# STM32_Schematic.net
KiCad netlist of a schematic drawn in Altium Designer
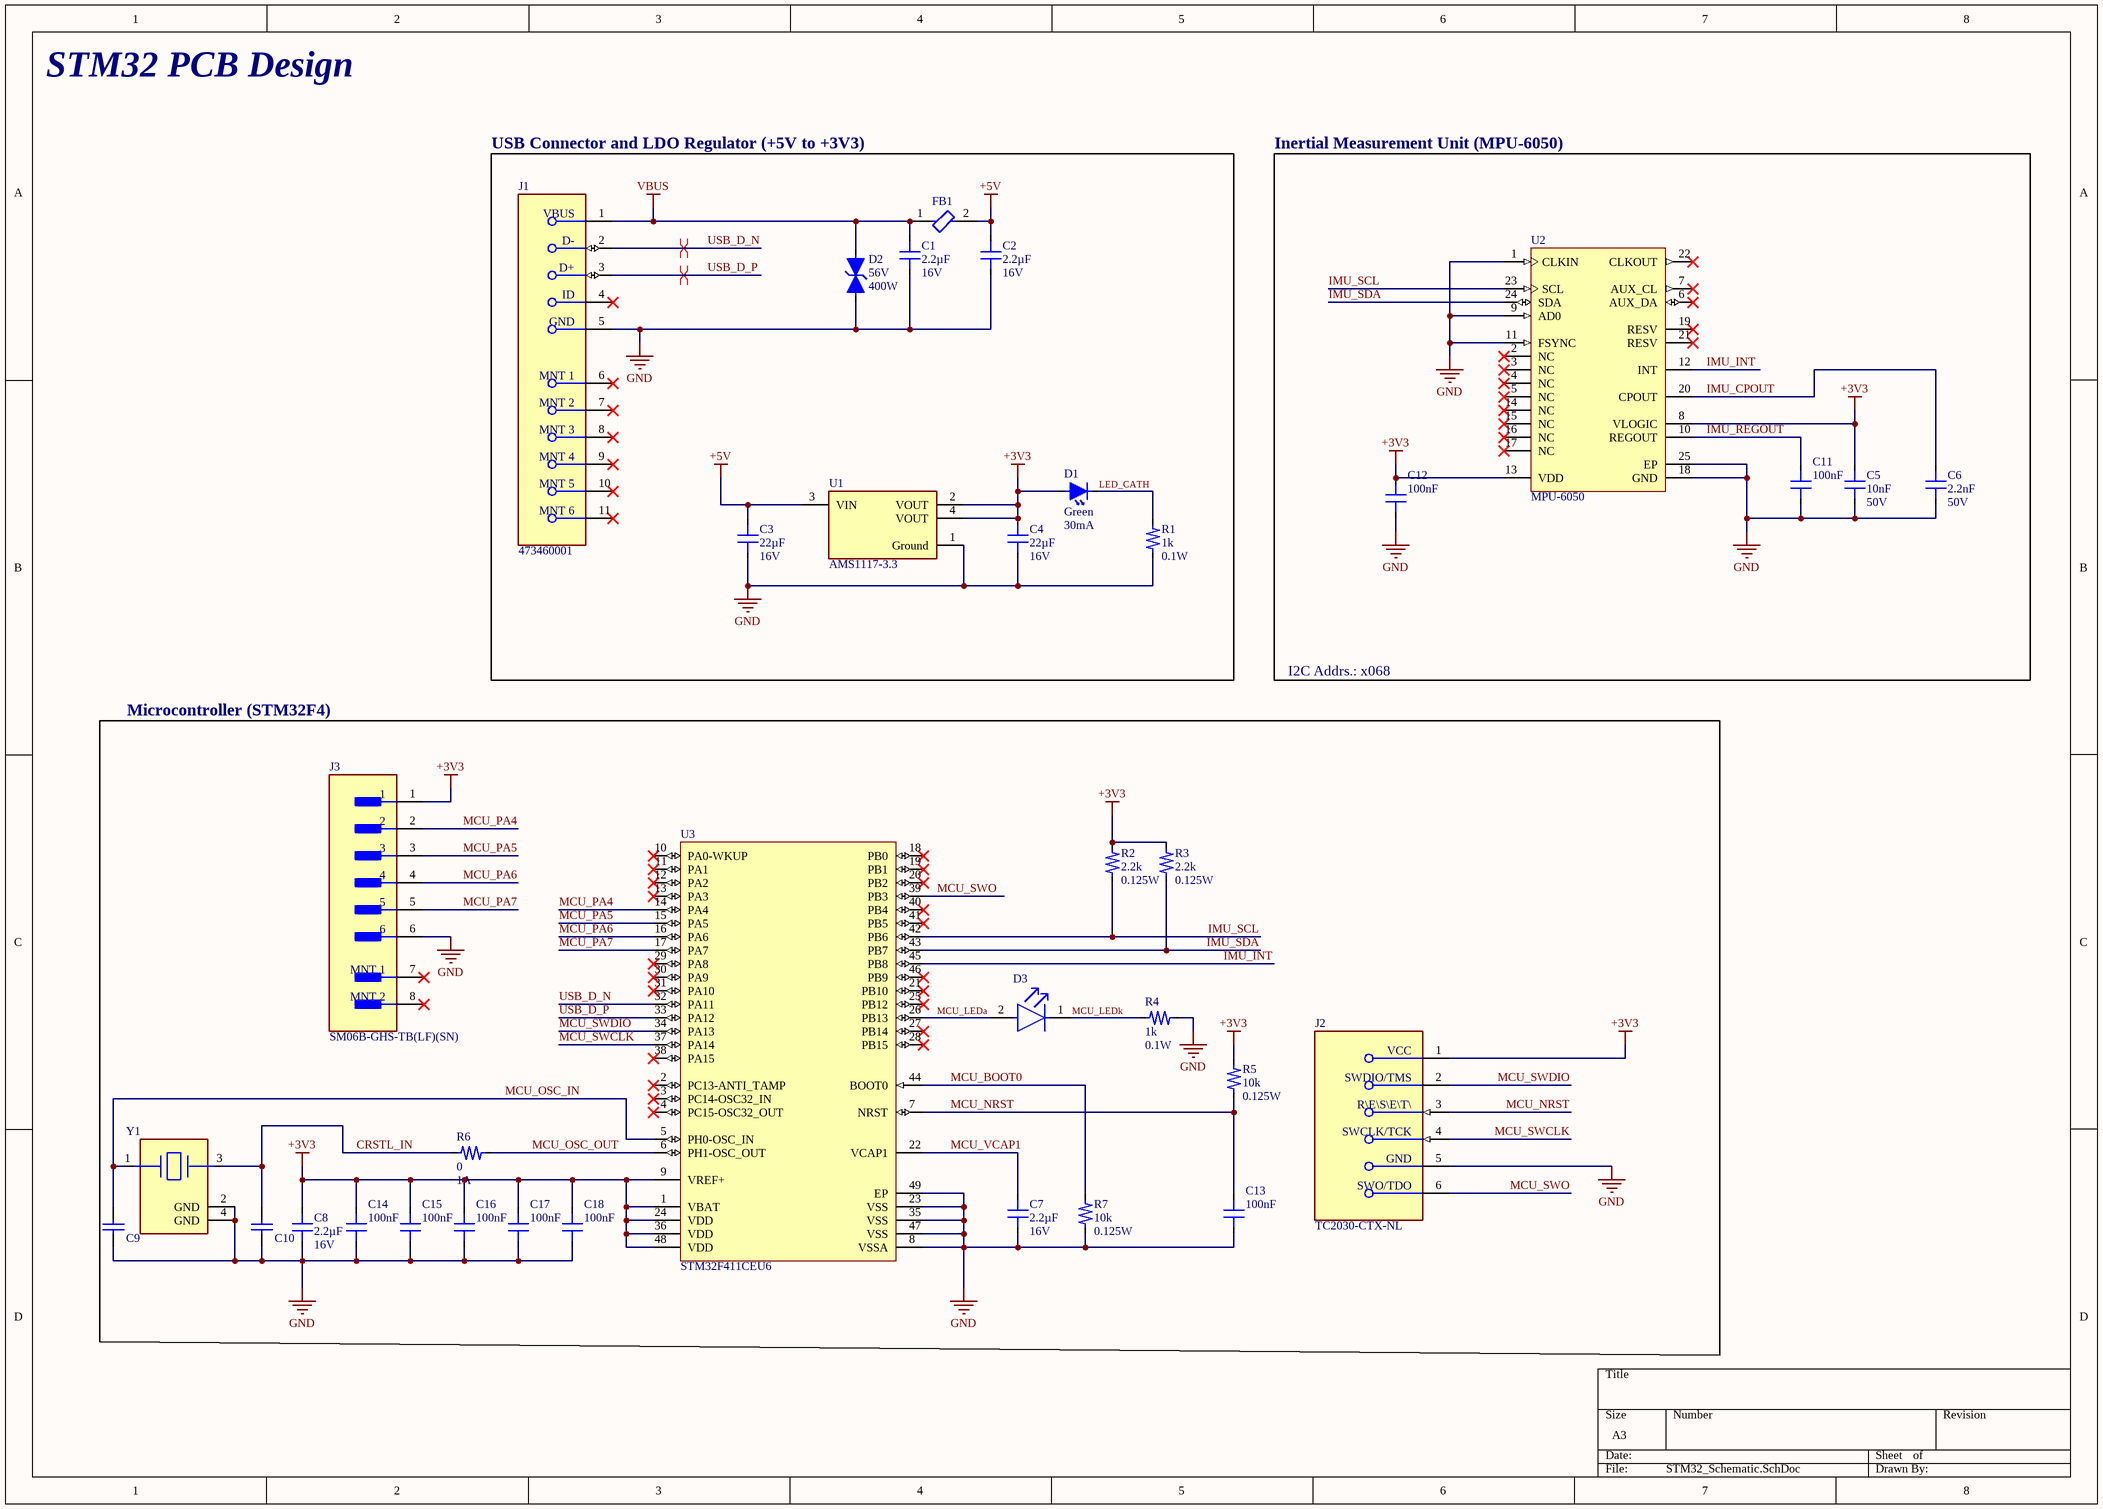
[diagram p0: STM32_Schematic.SchDoc]

(export (version "E")
  (design (tool "Eeschema 10.0.6"))
  (components
    (comp (ref "C1")
      (value "2.2µF")
      (footprint "C_0805")
      (fields
        (field (name "RATING") "16V")
        (field (name "PART NUMBER") "CC0805ZRY5V7BB225")
        (field (name "TOLERANCE") "20%")
      )
      (libsource (lib "BME Formula Racing Team") (part "CC0805ZRY5V7BB225"))
    )
    (comp (ref "C2")
      (value "2.2µF")
      (footprint "C_0805")
      (fields
        (field (name "RATING") "16V")
        (field (name "PART NUMBER") "CC0805ZRY5V7BB225")
        (field (name "TOLERANCE") "20%")
      )
      (libsource (lib "BME Formula Racing Team") (part "CC0805ZRY5V7BB225"))
    )
    (comp (ref "C3")
      (value "22µF")
      (footprint "C_1210")
      (fields
        (field (name "RATING") "16V")
        (field (name "TOLERANCE") "10%")
        (field (name "PART NUMBER") "CL32A226KOJNNNE")
      )
      (libsource (lib "BME Formula Racing Team") (part "CL32A226KOJNNNE"))
    )
    (comp (ref "C4")
      (value "22µF")
      (footprint "C_1210")
      (fields
        (field (name "RATING") "16V")
        (field (name "TOLERANCE") "10%")
        (field (name "PART NUMBER") "CL32A226KOJNNNE")
      )
      (libsource (lib "BME Formula Racing Team") (part "CL32A226KOJNNNE"))
    )
    (comp (ref "C5")
      (value "10nF")
      (footprint "C_0603")
      (fields
        (field (name "RATING") "50V")
        (field (name "PART NUMBER") "CC0603KRX7R9BB103")
        (field (name "TOLERANCE") "10%")
      )
      (libsource (lib "BME Formula Racing Team") (part "CC0603KRX7R9BB103"))
    )
    (comp (ref "C6")
      (value "2.2nF")
      (footprint "C_0805")
      (fields
        (field (name "RATING") "50V")
        (field (name "TOLERANCE") "5%")
        (field (name "PART NUMBER") "CC0805JKNP09BN222")
      )
      (libsource (lib "BME Formula Racing Team") (part "CC0805JKNP09BN222"))
    )
    (comp (ref "C7")
      (value "2.2µF")
      (footprint "C_0805")
      (fields
        (field (name "RATING") "16V")
        (field (name "PART NUMBER") "CC0805ZRY5V7BB225")
        (field (name "TOLERANCE") "20%")
      )
      (libsource (lib "BME Formula Racing Team") (part "CC0805ZRY5V7BB225"))
    )
    (comp (ref "C8")
      (value "2.2µF")
      (footprint "C_0805")
      (fields
        (field (name "RATING") "16V")
        (field (name "PART NUMBER") "CC0805ZRY5V7BB225")
        (field (name "TOLERANCE") "20%")
      )
      (libsource (lib "BME Formula Racing Team") (part "CC0805ZRY5V7BB225"))
    )
    (comp (ref "C9")
      (value "885392005106")
      (footprint "WCAP-CSRF_0402")
      (description "WCAP-CSRF Multilayer Ceramic Chip Capacitor High Frequency, size 0402, NP0 Class I, 10pF, 50VDC")
      (fields (field (name "MANUFACTURER") "Wurth Elektronik"))
      (libsource (lib "BME Formula Racing Team") (part "885392005147"))
    )
    (comp (ref "C10")
      (value "885392005106")
      (footprint "WCAP-CSRF_0402")
      (description "WCAP-CSRF Multilayer Ceramic Chip Capacitor High Frequency, size 0402, NP0 Class I, 10pF, 50VDC")
      (fields (field (name "MANUFACTURER") "Wurth Elektronik"))
      (libsource (lib "BME Formula Racing Team") (part "885392005147"))
    )
    (comp (ref "C11")
      (value "100nF")
      (footprint "CAPC1005X55N")
      (description "Multilayer Ceramic Capacitor, 0.1 uF, 16 V, ï¿½ 10%, X7R, 0402 [1005 Metric]")
      (fields (field (name "TOLERANCE") "10%") (field (name "MOUSER PART NUMBER") "187-CL05B104KO5NNNC"))
      (libsource (lib "BME Formula Racing Team") (part "CL10A105KA8NNNC"))
    )
    (comp (ref "C12")
      (value "100nF")
      (footprint "CAPC1005X55N")
      (description "Multilayer Ceramic Capacitor, 0.1 uF, 16 V, ï¿½ 10%, X7R, 0402 [1005 Metric]")
      (fields (field (name "TOLERANCE") "10%") (field (name "MOUSER PART NUMBER") "187-CL05B104KO5NNNC"))
      (libsource (lib "BME Formula Racing Team") (part "CL10A105KA8NNNC"))
    )
    (comp (ref "C13")
      (value "100nF")
      (footprint "CAPC1005X55N")
      (description "Multilayer Ceramic Capacitor, 0.1 uF, 16 V, ï¿½ 10%, X7R, 0402 [1005 Metric]")
      (fields (field (name "TOLERANCE") "10%") (field (name "MOUSER PART NUMBER") "187-CL05B104KO5NNNC"))
      (libsource (lib "BME Formula Racing Team") (part "CL10A105KA8NNNC"))
    )
    (comp (ref "C14")
      (value "100nF")
      (footprint "CAPC1005X55N")
      (description "Multilayer Ceramic Capacitor, 0.1 uF, 16 V, ï¿½ 10%, X7R, 0402 [1005 Metric]")
      (fields (field (name "TOLERANCE") "10%") (field (name "MOUSER PART NUMBER") "187-CL05B104KO5NNNC"))
      (libsource (lib "BME Formula Racing Team") (part "CL10A105KA8NNNC"))
    )
    (comp (ref "C15")
      (value "100nF")
      (footprint "CAPC1005X55N")
      (description "Multilayer Ceramic Capacitor, 0.1 uF, 16 V, ï¿½ 10%, X7R, 0402 [1005 Metric]")
      (fields (field (name "TOLERANCE") "10%") (field (name "MOUSER PART NUMBER") "187-CL05B104KO5NNNC"))
      (libsource (lib "BME Formula Racing Team") (part "CL10A105KA8NNNC"))
    )
    (comp (ref "C16")
      (value "100nF")
      (footprint "CAPC1005X55N")
      (description "Multilayer Ceramic Capacitor, 0.1 uF, 16 V, ï¿½ 10%, X7R, 0402 [1005 Metric]")
      (fields (field (name "TOLERANCE") "10%") (field (name "MOUSER PART NUMBER") "187-CL05B104KO5NNNC"))
      (libsource (lib "BME Formula Racing Team") (part "CL10A105KA8NNNC"))
    )
    (comp (ref "C17")
      (value "100nF")
      (footprint "CAPC1005X55N")
      (description "Multilayer Ceramic Capacitor, 0.1 uF, 16 V, ï¿½ 10%, X7R, 0402 [1005 Metric]")
      (fields (field (name "TOLERANCE") "10%") (field (name "MOUSER PART NUMBER") "187-CL05B104KO5NNNC"))
      (libsource (lib "BME Formula Racing Team") (part "CL10A105KA8NNNC"))
    )
    (comp (ref "C18")
      (value "100nF")
      (footprint "CAPC1005X55N")
      (description "Multilayer Ceramic Capacitor, 0.1 uF, 16 V, ï¿½ 10%, X7R, 0402 [1005 Metric]")
      (fields (field (name "TOLERANCE") "10%") (field (name "MOUSER PART NUMBER") "187-CL05B104KO5NNNC"))
      (libsource (lib "BME Formula Racing Team") (part "CL10A105KA8NNNC"))
    )
    (comp (ref "D1")
      (value "Green")
      (footprint "LED_0603")
      (fields (field (name "RATING") "30mA") (field (name "PART NUMBER") "FYLS-0603UGC"))
      (libsource (lib "BME Formula Racing Team") (part "FYLS-0603UGC"))
    )
    (comp (ref "D2")
      (value "56V")
      (footprint "SMA")
      (description "bidirectional")
      (fields (field (name "RATING") "400W") (field (name "PART NUMBER") "SMAJ48CA"))
      (libsource (lib "BME Formula Racing Team") (part "SMAJ5.0A"))
    )
    (comp (ref "D3")
      (value "LXZ1-PD02")
      (footprint "FP-LXZ1-PD02-MFG")
      (description "LUXEON Z High Power SMT LED Emitter Red Lambertian 500mA 2.15 V")
      (libsource (lib "Altium Content Vault") (part "8706943c75ba83719d021d2fdc84c58"))
    )
    (comp (ref "FB1")
      (value "MMZ1608R121ATA00")
      (footprint "FP-MMZ1608-0_8-IPC_C")
      (description "Signal Line Ferrite Bead 120Ω  @ 100MHz 500mA DCR 180mΩ SMD 0603")
      (fields (field (name "TOLERANCE") "25%"))
      (libsource (lib "Altium Content Vault") (part "5f30dd21d616792df468990f7003faa"))
    )
    (comp (ref "J1")
      (value "473460001")
      (footprint "FP-473460001-MFG")
      (description "CONN RCPT USB2.0 MICRO B SMD R/A")
      (fields
        (field (name "OCTOPART") "https://octopart.com/47346-0001-molex-7164928")
        (field (name "MANUFACTURER") "Molex")
      )
      (libsource (lib "Altium Content Vault") (part "53ae1f1d9b557310b43ca686e5bb76a"))
    )
    (comp (ref "J2")
      (value "TC2030-CTX-NL")
      (footprint "FP-TC2030-CTX-NL-MFG")
      (description "6-Pin “No legs” TC2030 Plug-of-Nails™ Cable for use with ARM Cortex processors")
      (libsource (lib "Altium Content Vault") (part "e3fe093a55dc37473f431e03719485e"))
    )
    (comp (ref "J3")
      (value "SM06B-GHS-TB(LF)(SN)")
      (footprint "FP-SM06B-GHS-TB_LF_SN-MFG")
      (description "CONN HEADER SMD R/A 6POS 1.25MM")
      (libsource (lib "Altium Content Vault") (part "ed24c53d9ba001d1a2a686240a95171"))
    )
    (comp (ref "R1")
      (value "1k")
      (footprint "R_0603")
      (fields
        (field (name "RATING") "0.1W")
        (field (name "NI PART NUMBER") "713776-01")
        (field (name "PART NUMBER") "CR-03FL7----1K")
        (field (name "TOLERANCE") "1%")
      )
      (libsource (lib "BME Formula Racing Team") (part "CR-03FL7----1K"))
    )
    (comp (ref "R2")
      (value "2.2k")
      (footprint "R_0805")
      (fields
        (field (name "RATING") "0.125W")
        (field (name "TOLERANCE") "1%")
        (field (name "PART NUMBER") "CR-05FL7---2K2")
      )
      (libsource (lib "BME Formula Racing Team") (part "CR-05FL7---2K2"))
    )
    (comp (ref "R3")
      (value "2.2k")
      (footprint "R_0805")
      (fields
        (field (name "RATING") "0.125W")
        (field (name "TOLERANCE") "1%")
        (field (name "PART NUMBER") "CR-05FL7---2K2")
      )
      (libsource (lib "BME Formula Racing Team") (part "CR-05FL7---2K2"))
    )
    (comp (ref "R4")
      (value "1k")
      (footprint "R_0603")
      (fields
        (field (name "RATING") "0.1W")
        (field (name "NI PART NUMBER") "713776-01")
        (field (name "PART NUMBER") "CR-03FL7----1K")
        (field (name "TOLERANCE") "1%")
      )
      (libsource (lib "") (part "CR-03FL7----1K_1"))
    )
    (comp (ref "R5")
      (value "10k")
      (footprint "R_0805")
      (fields
        (field (name "RATING") "0.125W")
        (field (name "PART NUMBER") "CR-05FL7---10K")
        (field (name "TOLERANCE") "1%")
      )
      (libsource (lib "BME Formula Racing Team") (part "CR-05FL7---10K"))
    )
    (comp (ref "R6")
      (value "0")
      (footprint "R_0603")
      (fields
        (field (name "RATING") "1A")
        (field (name "PART NUMBER") "CR-03JL7----0R")
        (field (name "NI PART NUMBER") "611560-01")
        (field (name "TOLERANCE") "5%")
      )
      (libsource (lib "BME Formula Racing Team") (part "CR-03JL7----0R"))
    )
    (comp (ref "R7")
      (value "10k")
      (footprint "R_0805")
      (fields
        (field (name "RATING") "0.125W")
        (field (name "PART NUMBER") "CR-05FL7---10K")
        (field (name "TOLERANCE") "1%")
      )
      (libsource (lib "BME Formula Racing Team") (part "CR-05FL7---10K"))
    )
    (comp (ref "U1")
      (value "AMS1117-3.3")
      (footprint "FP-AMS1117-IPC_C")
      (description "LDO Voltage Regulators 1A, 3.3V")
      (fields
        (field (name "OCTOPART") "https://octopart.com/ams1117-3.3-advanced+monolithic+systems-25899300")
        (field (name "MANUFACTURER") "Advanced Monolithic Systems")
      )
      (libsource (lib "Altium Content Vault") (part "8bdbb5f8e77002000e30dd2845d0354"))
    )
    (comp (ref "U2")
      (value "MPU-6050")
      (footprint "IS-QFN-24_V")
      (fields (field (name "MANUFACTURER") "InvenSense"))
      (libsource (lib "Altium Content Vault") (part "IS-MPU-6050-QFN-24"))
    )
    (comp (ref "U3")
      (value "STM32F411CEU6")
      (footprint "STM-UFQFPN48_L")
      (libsource (lib "Altium Content Vault") (part "MC-ARM-STM32F411-UFQFPN48"))
    )
    (comp (ref "Y1")
      (value "ABM11-20.000MHZ-B7G-T")
      (footprint "FP-ABM11-MFG")
      (description "Crystal 20MHz ±15ppm 10pF SMD-4 2mm x 1.6mm")
      (fields (field (name "TOLERANCE") "15ppm"))
      (libsource (lib "Altium Content Vault") (part "b3c1237d77310e73098bcf11eecb25f"))
    )
  )
  (nets
    (net (code "1") (name "+3V3") (class "Default")
      (node (ref "C12") (pin "1") (pinfunction "C1_1") (pintype "passive"))
      (node (ref "C14") (pin "1") (pinfunction "C1_1") (pintype "passive"))
      (node (ref "C15") (pin "1") (pinfunction "C1_1") (pintype "passive"))
      (node (ref "C16") (pin "1") (pinfunction "C1_1") (pintype "passive"))
      (node (ref "C17") (pin "1") (pinfunction "C1_1") (pintype "passive"))
      (node (ref "C18") (pin "1") (pinfunction "C1_1") (pintype "passive"))
      (node (ref "C4") (pin "2") (pinfunction "C2_2") (pintype "passive"))
      (node (ref "C5") (pin "2") (pinfunction "C2_2") (pintype "passive"))
      (node (ref "C8") (pin "2") (pinfunction "C2_2") (pintype "passive"))
      (node (ref "D1") (pin "2") (pinfunction "DA_2") (pintype "passive"))
      (node (ref "J2") (pin "1") (pinfunction "VCC_1") (pintype "power_in"))
      (node (ref "J3") (pin "1") (pinfunction "1_1") (pintype "passive"))
      (node (ref "R2") (pin "2") (pinfunction "R2_2") (pintype "passive"))
      (node (ref "R3") (pin "2") (pinfunction "R2_2") (pintype "passive"))
      (node (ref "R5") (pin "2") (pinfunction "R2_2") (pintype "passive"))
      (node (ref "U1") (pin "2") (pinfunction "VOUT_2") (pintype "passive"))
      (node (ref "U1") (pin "4") (pinfunction "VOUT_4") (pintype "passive"))
      (node (ref "U2") (pin "13") (pinfunction "VDD_13") (pintype "power_in"))
      (node (ref "U2") (pin "8") (pinfunction "VLOGIC_8") (pintype "power_in"))
      (node (ref "U3") (pin "1") (pinfunction "VBAT_1") (pintype "power_in"))
      (node (ref "U3") (pin "24") (pinfunction "VDD_24") (pintype "power_in"))
      (node (ref "U3") (pin "36") (pinfunction "VDD_36") (pintype "power_in"))
      (node (ref "U3") (pin "48") (pinfunction "VDD_48") (pintype "power_in"))
      (node (ref "U3") (pin "9") (pinfunction "VREF+_9") (pintype "power_in"))
    )
    (net (code "2") (name "+5V") (class "Default")
      (node (ref "C2") (pin "2") (pinfunction "C2_2") (pintype "passive"))
      (node (ref "C3") (pin "2") (pinfunction "C2_2") (pintype "passive"))
      (node (ref "FB1") (pin "2") (pinfunction "2_2") (pintype "passive"))
      (node (ref "U1") (pin "3") (pinfunction "VIN_3") (pintype "power_in"))
    )
    (net (code "3") (name "/CRSTL_IN") (class "Default")
      (node (ref "C10") (pin "2") (pinfunction "2_2") (pintype "passive"))
      (node (ref "R6") (pin "1") (pinfunction "R1_1") (pintype "passive"))
      (node (ref "Y1") (pin "3") (pinfunction "3_3") (pintype "passive"))
    )
    (net (code "4") (name "/IMU_CPOUT") (class "Default")
      (node (ref "C6") (pin "2") (pinfunction "C2_2") (pintype "passive"))
      (node (ref "U2") (pin "20") (pinfunction "CPOUT_20") (pintype "passive"))
    )
    (net (code "5") (name "/IMU_INT") (class "Default")
      (node (ref "U2") (pin "12") (pinfunction "INT_12") (pintype "open_collector"))
      (node (ref "U3") (pin "45") (pinfunction "PB8_45") (pintype "bidirectional"))
    )
    (net (code "6") (name "/IMU_REGOUT") (class "Default")
      (node (ref "C11") (pin "1") (pinfunction "C1_1") (pintype "passive"))
      (node (ref "U2") (pin "10") (pinfunction "REGOUT_10") (pintype "passive"))
    )
    (net (code "7") (name "/IMU_SCL") (class "Default")
      (node (ref "R2") (pin "1") (pinfunction "R1_1") (pintype "passive"))
      (node (ref "U2") (pin "23") (pinfunction "SCL_23") (pintype "input"))
      (node (ref "U3") (pin "42") (pinfunction "PB6_42") (pintype "bidirectional"))
    )
    (net (code "8") (name "/IMU_SDA") (class "Default")
      (node (ref "R3") (pin "1") (pinfunction "R1_1") (pintype "passive"))
      (node (ref "U2") (pin "24") (pinfunction "SDA_24") (pintype "bidirectional"))
      (node (ref "U3") (pin "43") (pinfunction "PB7_43") (pintype "bidirectional"))
    )
    (net (code "9") (name "/LED_CATH") (class "Default")
      (node (ref "D1") (pin "1") (pinfunction "DC_1") (pintype "passive"))
      (node (ref "R1") (pin "2") (pinfunction "R2_2") (pintype "passive"))
    )
    (net (code "10") (name "/MCU_BOOT0") (class "Default")
      (node (ref "R7") (pin "2") (pinfunction "R2_2") (pintype "passive"))
      (node (ref "U3") (pin "44") (pinfunction "BOOT0_44") (pintype "input"))
    )
    (net (code "11") (name "/MCU_LEDa") (class "Default")
      (node (ref "D3") (pin "2") (pinfunction "A_2") (pintype "passive"))
      (node (ref "U3") (pin "26") (pinfunction "PB13_26") (pintype "bidirectional"))
    )
    (net (code "12") (name "/MCU_LEDk") (class "Default")
      (node (ref "D3") (pin "1") (pinfunction "C_1") (pintype "passive"))
      (node (ref "R4") (pin "2") (pinfunction "R2_2") (pintype "passive"))
    )
    (net (code "13") (name "/MCU_NRST") (class "Default")
      (node (ref "C13") (pin "1") (pinfunction "C1_1") (pintype "passive"))
      (node (ref "J2") (pin "3") (pinfunction "~{RESET}_3") (pintype "input"))
      (node (ref "R5") (pin "1") (pinfunction "R1_1") (pintype "passive"))
      (node (ref "U3") (pin "7") (pinfunction "NRST_7") (pintype "bidirectional"))
    )
    (net (code "14") (name "/MCU_OSC_IN") (class "Default")
      (node (ref "C9") (pin "2") (pinfunction "2_2") (pintype "passive"))
      (node (ref "U3") (pin "5") (pinfunction "PH0-OSC_IN_5") (pintype "bidirectional"))
      (node (ref "Y1") (pin "1") (pinfunction "1_1") (pintype "passive"))
    )
    (net (code "15") (name "/MCU_OSC_OUT") (class "Default")
      (node (ref "R6") (pin "2") (pinfunction "R2_2") (pintype "passive"))
      (node (ref "U3") (pin "6") (pinfunction "PH1-OSC_OUT_6") (pintype "bidirectional"))
    )
    (net (code "16") (name "/MCU_PA4") (class "Default")
      (node (ref "J3") (pin "2") (pinfunction "2_2") (pintype "passive"))
      (node (ref "U3") (pin "14") (pinfunction "PA4_14") (pintype "bidirectional"))
    )
    (net (code "17") (name "/MCU_PA5") (class "Default")
      (node (ref "J3") (pin "3") (pinfunction "3_3") (pintype "passive"))
      (node (ref "U3") (pin "15") (pinfunction "PA5_15") (pintype "bidirectional"))
    )
    (net (code "18") (name "/MCU_PA6") (class "Default")
      (node (ref "J3") (pin "4") (pinfunction "4_4") (pintype "passive"))
      (node (ref "U3") (pin "16") (pinfunction "PA6_16") (pintype "bidirectional"))
    )
    (net (code "19") (name "/MCU_PA7") (class "Default")
      (node (ref "J3") (pin "5") (pinfunction "5_5") (pintype "passive"))
      (node (ref "U3") (pin "17") (pinfunction "PA7_17") (pintype "bidirectional"))
    )
    (net (code "20") (name "/MCU_SWCLK") (class "Default")
      (node (ref "J2") (pin "4") (pinfunction "SWCLK/TCK_4") (pintype "input"))
      (node (ref "U3") (pin "37") (pinfunction "PA14_37") (pintype "bidirectional"))
    )
    (net (code "21") (name "/MCU_SWDIO") (class "Default")
      (node (ref "J2") (pin "2") (pinfunction "SWDIO/TMS_2") (pintype "passive"))
      (node (ref "U3") (pin "34") (pinfunction "PA13_34") (pintype "bidirectional"))
    )
    (net (code "22") (name "/MCU_SWO") (class "Default")
      (node (ref "J2") (pin "6") (pinfunction "SWO/TDO_6") (pintype "passive"))
      (node (ref "U3") (pin "39") (pinfunction "PB3_39") (pintype "bidirectional"))
    )
    (net (code "23") (name "/MCU_VCAP1") (class "Default")
      (node (ref "C7") (pin "2") (pinfunction "C2_2") (pintype "passive"))
      (node (ref "U3") (pin "22") (pinfunction "VCAP1_22") (pintype "passive"))
    )
    (net (code "24") (name "/USB_D_N") (class "Default")
      (node (ref "J1") (pin "2") (pinfunction "D-_2") (pintype "bidirectional"))
      (node (ref "U3") (pin "32") (pinfunction "PA11_32") (pintype "bidirectional"))
    )
    (net (code "25") (name "/USB_D_P") (class "Default")
      (node (ref "J1") (pin "3") (pinfunction "D+_3") (pintype "bidirectional"))
      (node (ref "U3") (pin "33") (pinfunction "PA12_33") (pintype "bidirectional"))
    )
    (net (code "26") (name "GND") (class "Default")
      (node (ref "C1") (pin "1") (pinfunction "C1_1") (pintype "passive"))
      (node (ref "C10") (pin "1") (pinfunction "1_1") (pintype "passive"))
      (node (ref "C11") (pin "2") (pinfunction "C2_2") (pintype "passive"))
      (node (ref "C12") (pin "2") (pinfunction "C2_2") (pintype "passive"))
      (node (ref "C13") (pin "2") (pinfunction "C2_2") (pintype "passive"))
      (node (ref "C14") (pin "2") (pinfunction "C2_2") (pintype "passive"))
      (node (ref "C15") (pin "2") (pinfunction "C2_2") (pintype "passive"))
      (node (ref "C16") (pin "2") (pinfunction "C2_2") (pintype "passive"))
      (node (ref "C17") (pin "2") (pinfunction "C2_2") (pintype "passive"))
      (node (ref "C18") (pin "2") (pinfunction "C2_2") (pintype "passive"))
      (node (ref "C2") (pin "1") (pinfunction "C1_1") (pintype "passive"))
      (node (ref "C3") (pin "1") (pinfunction "C1_1") (pintype "passive"))
      (node (ref "C4") (pin "1") (pinfunction "C1_1") (pintype "passive"))
      (node (ref "C5") (pin "1") (pinfunction "C1_1") (pintype "passive"))
      (node (ref "C6") (pin "1") (pinfunction "C1_1") (pintype "passive"))
      (node (ref "C7") (pin "1") (pinfunction "C1_1") (pintype "passive"))
      (node (ref "C8") (pin "1") (pinfunction "C1_1") (pintype "passive"))
      (node (ref "C9") (pin "1") (pinfunction "1_1") (pintype "passive"))
      (node (ref "D2") (pin "2") (pinfunction "DA_2") (pintype "passive"))
      (node (ref "J1") (pin "5") (pinfunction "GND_5") (pintype "power_in"))
      (node (ref "J2") (pin "5") (pinfunction "GND_5") (pintype "power_in"))
      (node (ref "J3") (pin "6") (pinfunction "6_6") (pintype "passive"))
      (node (ref "R1") (pin "1") (pinfunction "R1_1") (pintype "passive"))
      (node (ref "R4") (pin "1") (pinfunction "R1_1") (pintype "passive"))
      (node (ref "R7") (pin "1") (pinfunction "R1_1") (pintype "passive"))
      (node (ref "U1") (pin "1") (pinfunction "Ground_1") (pintype "power_in"))
      (node (ref "U2") (pin "1") (pinfunction "CLKIN_1") (pintype "input"))
      (node (ref "U2") (pin "11") (pinfunction "FSYNC_11") (pintype "input"))
      (node (ref "U2") (pin "18") (pinfunction "GND_18") (pintype "power_in"))
      (node (ref "U2") (pin "25") (pinfunction "EP_25") (pintype "power_in"))
      (node (ref "U2") (pin "9") (pinfunction "AD0_9") (pintype "input"))
      (node (ref "U3") (pin "23") (pinfunction "VSS_23") (pintype "power_in"))
      (node (ref "U3") (pin "35") (pinfunction "VSS_35") (pintype "power_in"))
      (node (ref "U3") (pin "47") (pinfunction "VSS_47") (pintype "power_in"))
      (node (ref "U3") (pin "49") (pinfunction "EP_49") (pintype "power_in"))
      (node (ref "U3") (pin "8") (pinfunction "VSSA_8") (pintype "power_in"))
      (node (ref "Y1") (pin "2") (pinfunction "GND_2") (pintype "power_in"))
      (node (ref "Y1") (pin "4") (pinfunction "GND_4") (pintype "power_in"))
    )
    (net (code "27") (name "VBUS") (class "Default")
      (node (ref "C1") (pin "2") (pinfunction "C2_2") (pintype "passive"))
      (node (ref "D2") (pin "1") (pinfunction "DC_1") (pintype "passive"))
      (node (ref "FB1") (pin "1") (pinfunction "1_1") (pintype "passive"))
      (node (ref "J1") (pin "1") (pinfunction "VBUS_1") (pintype "power_in"))
    )
    (net (code "28") (name "unconnected-(J1-ID-Pad4)") (class "Default")
      (node (ref "J1") (pin "4") (pinfunction "ID_4") (pintype "passive+no_connect"))
    )
    (net (code "29") (name "unconnected-(J1-MNT_1-Pad6)") (class "Default")
      (node (ref "J1") (pin "6") (pinfunction "MNT_1_6") (pintype "passive+no_connect"))
    )
    (net (code "30") (name "unconnected-(J1-MNT_2-Pad7)") (class "Default")
      (node (ref "J1") (pin "7") (pinfunction "MNT_2_7") (pintype "passive+no_connect"))
    )
    (net (code "31") (name "unconnected-(J1-MNT_3-Pad8)") (class "Default")
      (node (ref "J1") (pin "8") (pinfunction "MNT_3_8") (pintype "passive+no_connect"))
    )
    (net (code "32") (name "unconnected-(J1-MNT_4-Pad9)") (class "Default")
      (node (ref "J1") (pin "9") (pinfunction "MNT_4_9") (pintype "passive+no_connect"))
    )
    (net (code "33") (name "unconnected-(J1-MNT_5-Pad10)") (class "Default")
      (node (ref "J1") (pin "10") (pinfunction "MNT_5_10") (pintype "passive+no_connect"))
    )
    (net (code "34") (name "unconnected-(J1-MNT_6-Pad11)") (class "Default")
      (node (ref "J1") (pin "11") (pinfunction "MNT_6_11") (pintype "passive+no_connect"))
    )
    (net (code "35") (name "unconnected-(J3-MNT_1-Pad7)") (class "Default")
      (node (ref "J3") (pin "7") (pinfunction "MNT_1_7") (pintype "passive+no_connect"))
    )
    (net (code "36") (name "unconnected-(J3-MNT_2-Pad8)") (class "Default")
      (node (ref "J3") (pin "8") (pinfunction "MNT_2_8") (pintype "passive+no_connect"))
    )
    (net (code "37") (name "unconnected-(U2-AUX_CL-Pad7)") (class "Default")
      (node (ref "U2") (pin "7") (pinfunction "AUX_CL_7") (pintype "output+no_connect"))
    )
    (net (code "38") (name "unconnected-(U2-AUX_DA-Pad6)") (class "Default")
      (node (ref "U2") (pin "6") (pinfunction "AUX_DA_6") (pintype "bidirectional+no_connect"))
    )
    (net (code "39") (name "unconnected-(U2-CLKOUT-Pad22)") (class "Default")
      (node (ref "U2") (pin "22") (pinfunction "CLKOUT_22") (pintype "output+no_connect"))
    )
    (net (code "40") (name "unconnected-(U2-NC-Pad2)") (class "Default")
      (node (ref "U2") (pin "2") (pinfunction "NC_2") (pintype "passive+no_connect"))
    )
    (net (code "41") (name "unconnected-(U2-NC-Pad3)") (class "Default")
      (node (ref "U2") (pin "3") (pinfunction "NC_3") (pintype "passive+no_connect"))
    )
    (net (code "42") (name "unconnected-(U2-NC-Pad4)") (class "Default")
      (node (ref "U2") (pin "4") (pinfunction "NC_4") (pintype "passive+no_connect"))
    )
    (net (code "43") (name "unconnected-(U2-NC-Pad5)") (class "Default")
      (node (ref "U2") (pin "5") (pinfunction "NC_5") (pintype "passive+no_connect"))
    )
    (net (code "44") (name "unconnected-(U2-NC-Pad14)") (class "Default")
      (node (ref "U2") (pin "14") (pinfunction "NC_14") (pintype "passive+no_connect"))
    )
    (net (code "45") (name "unconnected-(U2-NC-Pad15)") (class "Default")
      (node (ref "U2") (pin "15") (pinfunction "NC_15") (pintype "passive+no_connect"))
    )
    (net (code "46") (name "unconnected-(U2-NC-Pad16)") (class "Default")
      (node (ref "U2") (pin "16") (pinfunction "NC_16") (pintype "passive+no_connect"))
    )
    (net (code "47") (name "unconnected-(U2-NC-Pad17)") (class "Default")
      (node (ref "U2") (pin "17") (pinfunction "NC_17") (pintype "passive+no_connect"))
    )
    (net (code "48") (name "unconnected-(U2-RESV-Pad19)") (class "Default")
      (node (ref "U2") (pin "19") (pinfunction "RESV_19") (pintype "passive+no_connect"))
    )
    (net (code "49") (name "unconnected-(U2-RESV-Pad21)") (class "Default")
      (node (ref "U2") (pin "21") (pinfunction "RESV_21") (pintype "passive+no_connect"))
    )
    (net (code "50") (name "unconnected-(U3-PA0-WKUP-Pad10)") (class "Default")
      (node (ref "U3") (pin "10") (pinfunction "PA0-WKUP_10") (pintype "bidirectional+no_connect"))
    )
    (net (code "51") (name "unconnected-(U3-PA1-Pad11)") (class "Default")
      (node (ref "U3") (pin "11") (pinfunction "PA1_11") (pintype "bidirectional+no_connect"))
    )
    (net (code "52") (name "unconnected-(U3-PA2-Pad12)") (class "Default")
      (node (ref "U3") (pin "12") (pinfunction "PA2_12") (pintype "bidirectional+no_connect"))
    )
    (net (code "53") (name "unconnected-(U3-PA3-Pad13)") (class "Default")
      (node (ref "U3") (pin "13") (pinfunction "PA3_13") (pintype "bidirectional+no_connect"))
    )
    (net (code "54") (name "unconnected-(U3-PA8-Pad29)") (class "Default")
      (node (ref "U3") (pin "29") (pinfunction "PA8_29") (pintype "bidirectional+no_connect"))
    )
    (net (code "55") (name "unconnected-(U3-PA9-Pad30)") (class "Default")
      (node (ref "U3") (pin "30") (pinfunction "PA9_30") (pintype "bidirectional+no_connect"))
    )
    (net (code "56") (name "unconnected-(U3-PA10-Pad31)") (class "Default")
      (node (ref "U3") (pin "31") (pinfunction "PA10_31") (pintype "bidirectional+no_connect"))
    )
    (net (code "57") (name "unconnected-(U3-PA15-Pad38)") (class "Default")
      (node (ref "U3") (pin "38") (pinfunction "PA15_38") (pintype "bidirectional+no_connect"))
    )
    (net (code "58") (name "unconnected-(U3-PB0-Pad18)") (class "Default")
      (node (ref "U3") (pin "18") (pinfunction "PB0_18") (pintype "bidirectional+no_connect"))
    )
    (net (code "59") (name "unconnected-(U3-PB1-Pad19)") (class "Default")
      (node (ref "U3") (pin "19") (pinfunction "PB1_19") (pintype "bidirectional+no_connect"))
    )
    (net (code "60") (name "unconnected-(U3-PB2-Pad20)") (class "Default")
      (node (ref "U3") (pin "20") (pinfunction "PB2_20") (pintype "bidirectional+no_connect"))
    )
    (net (code "61") (name "unconnected-(U3-PB4-Pad40)") (class "Default")
      (node (ref "U3") (pin "40") (pinfunction "PB4_40") (pintype "bidirectional+no_connect"))
    )
    (net (code "62") (name "unconnected-(U3-PB5-Pad41)") (class "Default")
      (node (ref "U3") (pin "41") (pinfunction "PB5_41") (pintype "bidirectional+no_connect"))
    )
    (net (code "63") (name "unconnected-(U3-PB9-Pad46)") (class "Default")
      (node (ref "U3") (pin "46") (pinfunction "PB9_46") (pintype "bidirectional+no_connect"))
    )
    (net (code "64") (name "unconnected-(U3-PB10-Pad21)") (class "Default")
      (node (ref "U3") (pin "21") (pinfunction "PB10_21") (pintype "bidirectional+no_connect"))
    )
    (net (code "65") (name "unconnected-(U3-PB12-Pad25)") (class "Default")
      (node (ref "U3") (pin "25") (pinfunction "PB12_25") (pintype "bidirectional+no_connect"))
    )
    (net (code "66") (name "unconnected-(U3-PB14-Pad27)") (class "Default")
      (node (ref "U3") (pin "27") (pinfunction "PB14_27") (pintype "bidirectional+no_connect"))
    )
    (net (code "67") (name "unconnected-(U3-PB15-Pad28)") (class "Default")
      (node (ref "U3") (pin "28") (pinfunction "PB15_28") (pintype "bidirectional+no_connect"))
    )
    (net (code "68") (name "unconnected-(U3-PC13-ANTI_TAMP-Pad2)") (class "Default")
      (node (ref "U3") (pin "2") (pinfunction "PC13-ANTI_TAMP_2") (pintype "bidirectional+no_connect"))
    )
    (net (code "69") (name "unconnected-(U3-PC14-OSC32_IN-Pad3)") (class "Default")
      (node (ref "U3") (pin "3") (pinfunction "PC14-OSC32_IN_3") (pintype "bidirectional+no_connect"))
    )
    (net (code "70") (name "unconnected-(U3-PC15-OSC32_OUT-Pad4)") (class "Default")
      (node (ref "U3") (pin "4") (pinfunction "PC15-OSC32_OUT_4") (pintype "bidirectional+no_connect"))
    )
  )
)
